# LCR_0.net
KiCad netlist of a schematic drawn in Altium Designer
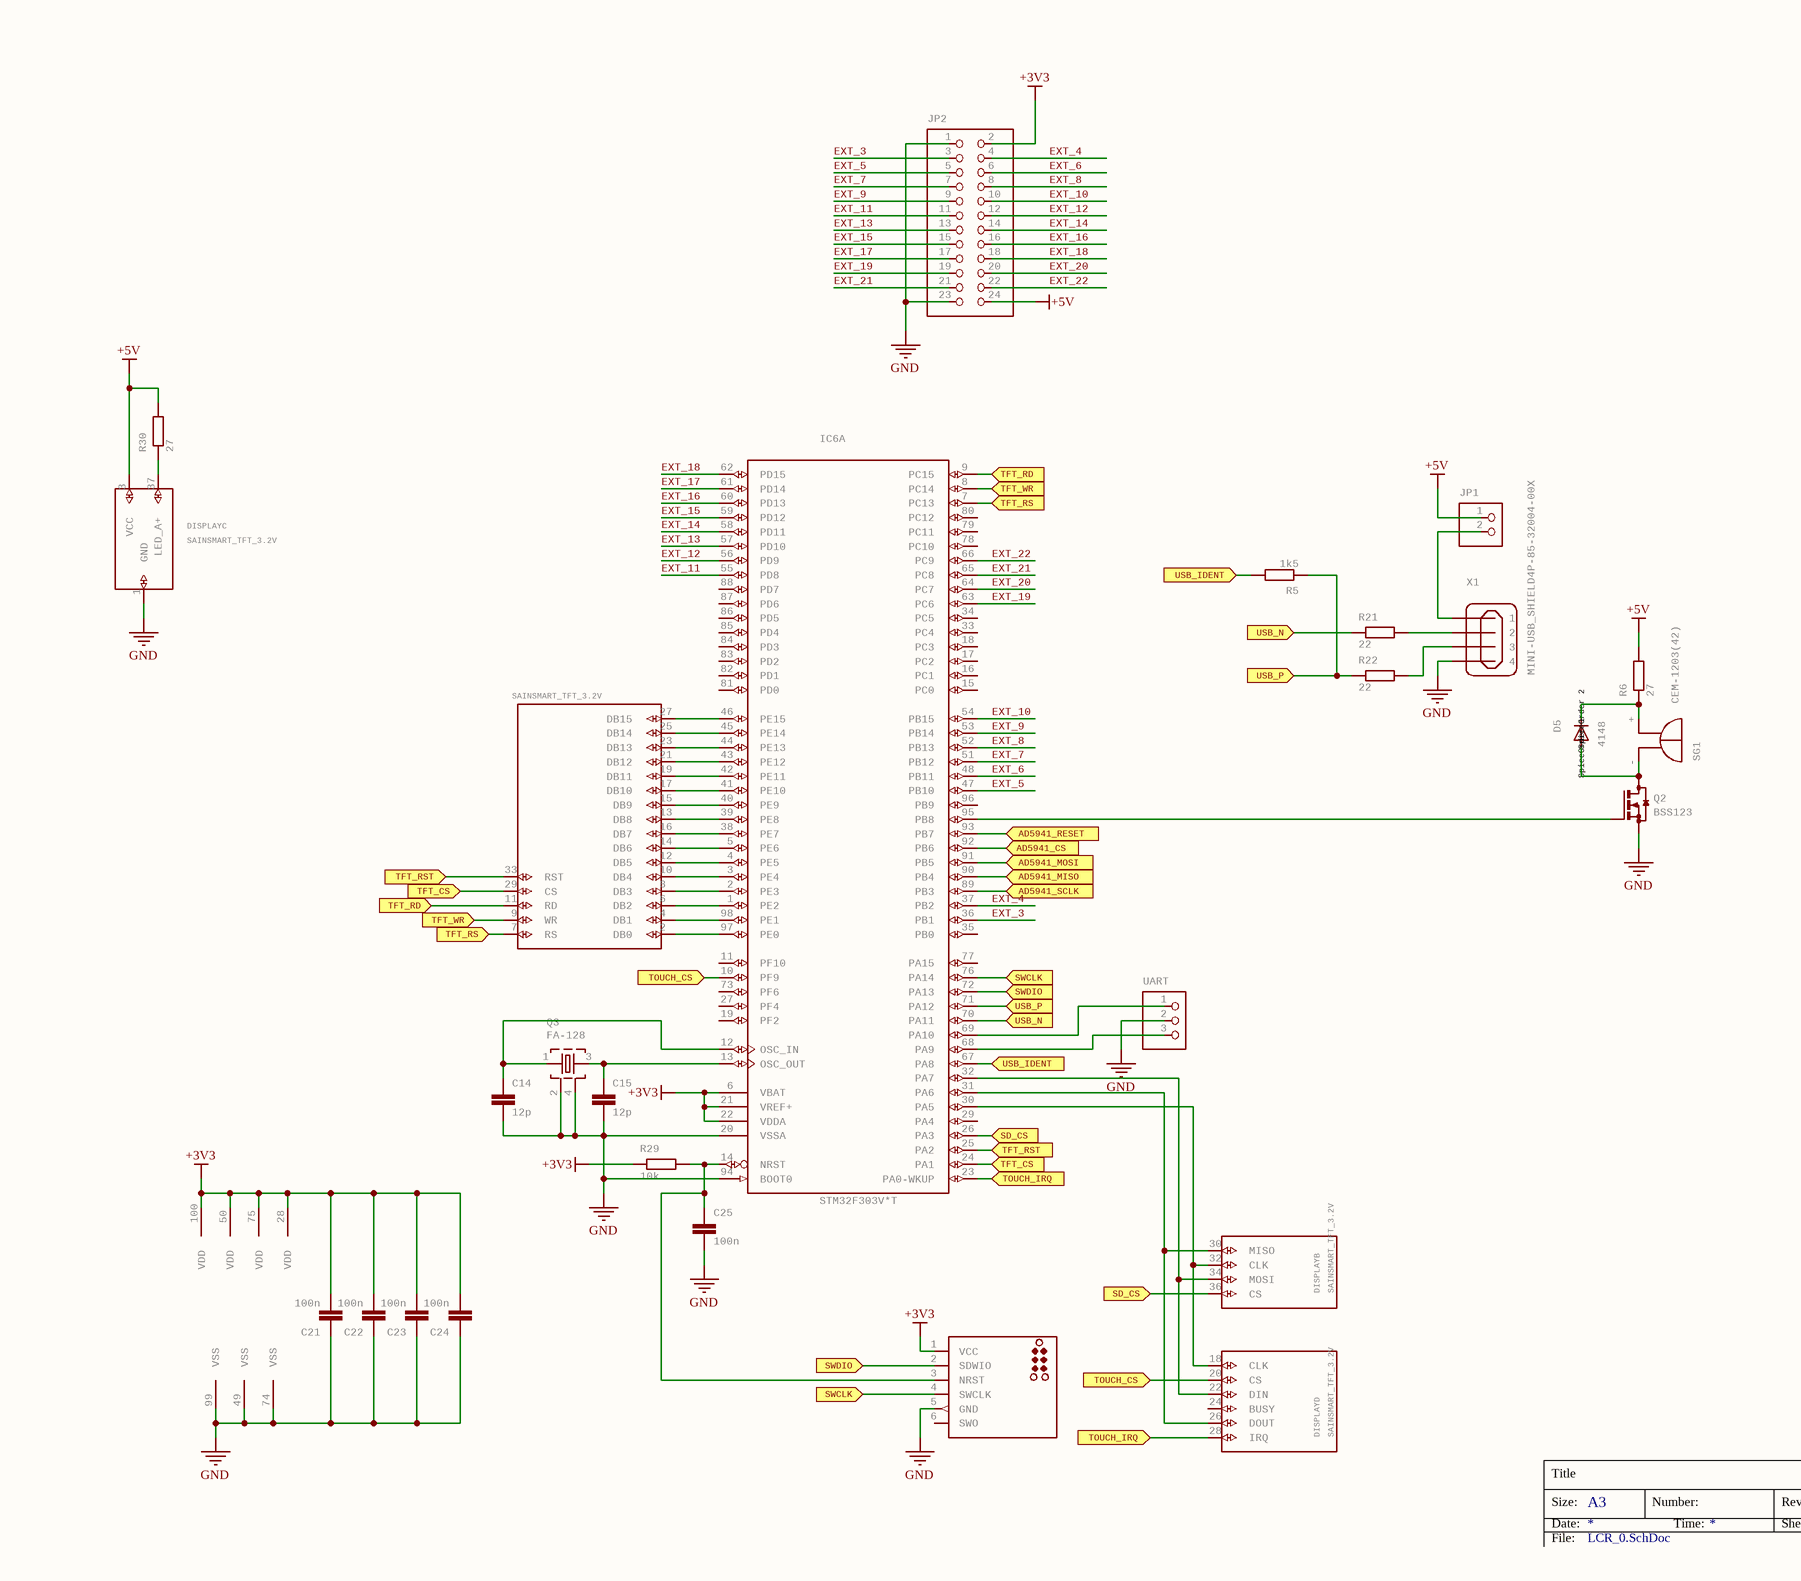
[diagram p0: LCR_0.SchDoc]

(export (version "E")
  (design (tool "Eeschema 10.0.6"))
  (components
    (comp (ref "C14")
      (value "12p")
      (footprint "C0603K")
      (description "CAPACITOR, European symbol")
      (libsource (lib "") (part "C-EUC0603K_1"))
    )
    (comp (ref "C15")
      (value "12p")
      (footprint "C0603K")
      (description "CAPACITOR, European symbol")
      (libsource (lib "") (part "C-EUC0603K_1"))
    )
    (comp (ref "C21")
      (value "100n")
      (footprint "C0603K")
      (description "CAPACITOR, European symbol")
      (libsource (lib "rcl") (part "C-EUC0603K"))
    )
    (comp (ref "C22")
      (value "100n")
      (footprint "C0603K")
      (description "CAPACITOR, European symbol")
      (libsource (lib "rcl") (part "C-EUC0603K"))
    )
    (comp (ref "C23")
      (value "100n")
      (footprint "C0603K")
      (description "CAPACITOR, European symbol")
      (libsource (lib "rcl") (part "C-EUC0603K"))
    )
    (comp (ref "C24")
      (value "100n")
      (footprint "C0603K")
      (description "CAPACITOR, European symbol")
      (libsource (lib "rcl") (part "C-EUC0603K"))
    )
    (comp (ref "C25")
      (value "100n")
      (footprint "C0603K")
      (description "CAPACITOR, European symbol")
      (libsource (lib "") (part "C-EUC0603K_1"))
    )
    (comp (ref "D5")
      (value "4148")
      (footprint "SOD123")
      (description "DIODE")
      (fields (field (name "SPICEORDER1") "SpiceOrder 1") (field (name "SPICEORDER2") "SpiceOrder 2"))
      (libsource (lib "diode") (part "DIODE-SOD123"))
    )
    (comp (ref "DISPLAY")
      (value "SAINSMART_TFT_3.2V")
      (footprint "SAINSMART_ANGLED")
      (libsource (lib "sainsmart") (part "SAINSMART_TFT_3.2V"))
    )
    (comp (ref "IC6")
      (value "STM32F303V*T")
      (footprint "LQFP100")
      (libsource (lib "micro-stm_v3") (part "STM32F303V*T"))
    )
    (comp (ref "J1")
      (value "TC2030-MCP")
      (footprint "TC2030-MCP")
      (libsource (lib "tag-connect") (part "TC2030-MCP"))
    )
    (comp (ref "JP1")
      (value "~")
      (footprint "1X02")
      (description "PIN HEADER")
      (fields (field (name "LIBRARYNAME") "pinhead"))
      (libsource (lib "pinhead") (part "PINHD-1X2"))
    )
    (comp (ref "JP2")
      (value "~")
      (footprint "2X12")
      (description "PIN HEADER")
      (fields (field (name "LIBRARYNAME") "pinhead"))
      (libsource (lib "pinhead") (part "PINHD-2X12"))
    )
    (comp (ref "Q2")
      (value "BSS123")
      (footprint "SOT23")
      (description "N-CHANNEL MOS FET")
      (libsource (lib "transistor-small-signal") (part "BSS123"))
    )
    (comp (ref "Q3")
      (value "FA-128")
      (footprint "FA-128")
      (description "MHz RANGE CRYSTAL UNIT    Source: Epson Toyocom")
      (libsource (lib "crystal") (part "FA-128"))
    )
    (comp (ref "R5")
      (value "1k5")
      (footprint "R0603")
      (description "RESISTOR, European symbol")
      (libsource (lib "resistor") (part "R-EU_R0603"))
    )
    (comp (ref "R6")
      (value "27")
      (footprint "R1206")
      (description "RESISTOR, European symbol")
      (libsource (lib "resistor") (part "R-EU_R1206"))
    )
    (comp (ref "R21")
      (value "22")
      (footprint "R0603")
      (description "RESISTOR, European symbol")
      (libsource (lib "resistor") (part "R-EU_R0603"))
    )
    (comp (ref "R22")
      (value "22")
      (footprint "R0603")
      (description "RESISTOR, European symbol")
      (libsource (lib "resistor") (part "R-EU_R0603"))
    )
    (comp (ref "R29")
      (value "10k")
      (footprint "R0603")
      (description "RESISTOR, European symbol")
      (libsource (lib "resistor") (part "R-EU_R0603"))
    )
    (comp (ref "R30")
      (value "27")
      (footprint "R1206")
      (description "RESISTOR, European symbol")
      (libsource (lib "resistor") (part "R-EU_R1206"))
    )
    (comp (ref "SG1")
      (value "CEM-1203(42)")
      (footprint "F/QMBIII")
      (description "BUZZER    Source: Buerklin")
      (fields (field (name "MF") "MF") (field (name "MPN") "MPN"))
      (libsource (lib "buzzer") (part "F/QMBIII"))
    )
    (comp (ref "UART")
      (value "~")
      (footprint "1X03")
      (description "PIN HEADER")
      (fields (field (name "LIBRARYNAME") "pinhead"))
      (libsource (lib "pinhead") (part "PINHD-1X3"))
    )
    (comp (ref "X1")
      (value "MINI-USB_SHIELD4P-85-32004-00X")
      (footprint "85-32004-00X")
      (description "MINI USB 4 Pol.   Source: www.cypressindustries.com")
      (fields (field (name "MF") "MF") (field (name "MPN") "MPN"))
      (libsource (lib "con-cypressindustries") (part "MINI-USB_SHIELD4P-85-32004-00X"))
    )
  )
  (nets
    (net (code "1") (name "+3V3") (class "Default")
      (node (ref "C21") (pin "2") (pinfunction "2_2") (pintype "passive"))
      (node (ref "C22") (pin "2") (pinfunction "2_2") (pintype "passive"))
      (node (ref "C23") (pin "2") (pinfunction "2_2") (pintype "passive"))
      (node (ref "C24") (pin "2") (pinfunction "2_2") (pintype "passive"))
      (node (ref "IC6") (pin "100") (pinfunction "VDD_100") (pintype "power_in"))
      (node (ref "IC6") (pin "21") (pinfunction "VREF+_21") (pintype "power_in"))
      (node (ref "IC6") (pin "22") (pinfunction "VDDA_22") (pintype "power_in"))
      (node (ref "IC6") (pin "28") (pinfunction "VDD_28") (pintype "power_in"))
      (node (ref "IC6") (pin "50") (pinfunction "VDD_50") (pintype "power_in"))
      (node (ref "IC6") (pin "6") (pinfunction "VBAT_6") (pintype "power_in"))
      (node (ref "IC6") (pin "75") (pinfunction "VDD_75") (pintype "power_in"))
      (node (ref "J1") (pin "1") (pinfunction "VCC_1") (pintype "passive"))
      (node (ref "JP2") (pin "2") (pinfunction "2_2") (pintype "passive"))
      (node (ref "R29") (pin "1") (pinfunction "1_1") (pintype "passive"))
    )
    (net (code "2") (name "+5V") (class "Default")
      (node (ref "DISPLAY") (pin "3") (pinfunction "VCC_3") (pintype "bidirectional"))
      (node (ref "JP1") (pin "1") (pinfunction "1_1") (pintype "passive"))
      (node (ref "JP2") (pin "24") (pinfunction "24_24") (pintype "passive"))
      (node (ref "R30") (pin "2") (pinfunction "2_2") (pintype "passive"))
      (node (ref "R6") (pin "2") (pinfunction "2_2") (pintype "passive"))
    )
    (net (code "3") (name "/AD5941_CS") (class "Default")
      (node (ref "IC6") (pin "92") (pinfunction "PB6_92") (pintype "bidirectional"))
    )
    (net (code "4") (name "/AD5941_MISO") (class "Default")
      (node (ref "IC6") (pin "90") (pinfunction "PB4_90") (pintype "bidirectional"))
    )
    (net (code "5") (name "/AD5941_MOSI") (class "Default")
      (node (ref "IC6") (pin "91") (pinfunction "PB5_91") (pintype "bidirectional"))
    )
    (net (code "6") (name "/AD5941_RESET") (class "Default")
      (node (ref "IC6") (pin "93") (pinfunction "PB7_93") (pintype "bidirectional"))
    )
    (net (code "7") (name "/AD5941_SCLK") (class "Default")
      (node (ref "IC6") (pin "89") (pinfunction "PB3_89") (pintype "bidirectional"))
    )
    (net (code "8") (name "/EXT_3") (class "Default")
      (node (ref "IC6") (pin "36") (pinfunction "PB1_36") (pintype "bidirectional"))
      (node (ref "JP2") (pin "3") (pinfunction "3_3") (pintype "passive"))
    )
    (net (code "9") (name "/EXT_4") (class "Default")
      (node (ref "IC6") (pin "37") (pinfunction "PB2_37") (pintype "bidirectional"))
      (node (ref "JP2") (pin "4") (pinfunction "4_4") (pintype "passive"))
    )
    (net (code "10") (name "/EXT_5") (class "Default")
      (node (ref "IC6") (pin "47") (pinfunction "PB10_47") (pintype "bidirectional"))
      (node (ref "JP2") (pin "5") (pinfunction "5_5") (pintype "passive"))
    )
    (net (code "11") (name "/EXT_6") (class "Default")
      (node (ref "IC6") (pin "48") (pinfunction "PB11_48") (pintype "bidirectional"))
      (node (ref "JP2") (pin "6") (pinfunction "6_6") (pintype "passive"))
    )
    (net (code "12") (name "/EXT_7") (class "Default")
      (node (ref "IC6") (pin "51") (pinfunction "PB12_51") (pintype "bidirectional"))
      (node (ref "JP2") (pin "7") (pinfunction "7_7") (pintype "passive"))
    )
    (net (code "13") (name "/EXT_8") (class "Default")
      (node (ref "IC6") (pin "52") (pinfunction "PB13_52") (pintype "bidirectional"))
      (node (ref "JP2") (pin "8") (pinfunction "8_8") (pintype "passive"))
    )
    (net (code "14") (name "/EXT_9") (class "Default")
      (node (ref "IC6") (pin "53") (pinfunction "PB14_53") (pintype "bidirectional"))
      (node (ref "JP2") (pin "9") (pinfunction "9_9") (pintype "passive"))
    )
    (net (code "15") (name "/EXT_10") (class "Default")
      (node (ref "IC6") (pin "54") (pinfunction "PB15_54") (pintype "bidirectional"))
      (node (ref "JP2") (pin "10") (pinfunction "10_10") (pintype "passive"))
    )
    (net (code "16") (name "/EXT_11") (class "Default")
      (node (ref "IC6") (pin "55") (pinfunction "PD8_55") (pintype "bidirectional"))
      (node (ref "JP2") (pin "11") (pinfunction "11_11") (pintype "passive"))
    )
    (net (code "17") (name "/EXT_12") (class "Default")
      (node (ref "IC6") (pin "56") (pinfunction "PD9_56") (pintype "bidirectional"))
      (node (ref "JP2") (pin "12") (pinfunction "12_12") (pintype "passive"))
    )
    (net (code "18") (name "/EXT_13") (class "Default")
      (node (ref "IC6") (pin "57") (pinfunction "PD10_57") (pintype "bidirectional"))
      (node (ref "JP2") (pin "13") (pinfunction "13_13") (pintype "passive"))
    )
    (net (code "19") (name "/EXT_14") (class "Default")
      (node (ref "IC6") (pin "58") (pinfunction "PD11_58") (pintype "bidirectional"))
      (node (ref "JP2") (pin "14") (pinfunction "14_14") (pintype "passive"))
    )
    (net (code "20") (name "/EXT_15") (class "Default")
      (node (ref "IC6") (pin "59") (pinfunction "PD12_59") (pintype "bidirectional"))
      (node (ref "JP2") (pin "15") (pinfunction "15_15") (pintype "passive"))
    )
    (net (code "21") (name "/EXT_16") (class "Default")
      (node (ref "IC6") (pin "60") (pinfunction "PD13_60") (pintype "bidirectional"))
      (node (ref "JP2") (pin "16") (pinfunction "16_16") (pintype "passive"))
    )
    (net (code "22") (name "/EXT_17") (class "Default")
      (node (ref "IC6") (pin "61") (pinfunction "PD14_61") (pintype "bidirectional"))
      (node (ref "JP2") (pin "17") (pinfunction "17_17") (pintype "passive"))
    )
    (net (code "23") (name "/EXT_18") (class "Default")
      (node (ref "IC6") (pin "62") (pinfunction "PD15_62") (pintype "bidirectional"))
      (node (ref "JP2") (pin "18") (pinfunction "18_18") (pintype "passive"))
    )
    (net (code "24") (name "/EXT_19") (class "Default")
      (node (ref "IC6") (pin "63") (pinfunction "PC6_63") (pintype "bidirectional"))
      (node (ref "JP2") (pin "19") (pinfunction "19_19") (pintype "passive"))
    )
    (net (code "25") (name "/EXT_20") (class "Default")
      (node (ref "IC6") (pin "64") (pinfunction "PC7_64") (pintype "bidirectional"))
      (node (ref "JP2") (pin "20") (pinfunction "20_20") (pintype "passive"))
    )
    (net (code "26") (name "/EXT_21") (class "Default")
      (node (ref "IC6") (pin "65") (pinfunction "PC8_65") (pintype "bidirectional"))
      (node (ref "JP2") (pin "21") (pinfunction "21_21") (pintype "passive"))
    )
    (net (code "27") (name "/EXT_22") (class "Default")
      (node (ref "IC6") (pin "66") (pinfunction "PC9_66") (pintype "bidirectional"))
      (node (ref "JP2") (pin "22") (pinfunction "22_22") (pintype "passive"))
    )
    (net (code "28") (name "/SD_CS") (class "Default")
      (node (ref "DISPLAY") (pin "36") (pinfunction "CS_36") (pintype "bidirectional"))
      (node (ref "IC6") (pin "26") (pinfunction "PA3_26") (pintype "bidirectional"))
    )
    (net (code "29") (name "/SWCLK") (class "Default")
      (node (ref "IC6") (pin "76") (pinfunction "PA14_76") (pintype "bidirectional"))
      (node (ref "J1") (pin "4") (pinfunction "SWCLK_4") (pintype "bidirectional"))
    )
    (net (code "30") (name "/SWDIO") (class "Default")
      (node (ref "IC6") (pin "72") (pinfunction "PA13_72") (pintype "bidirectional"))
      (node (ref "J1") (pin "2") (pinfunction "SDWIO_2") (pintype "power_in"))
    )
    (net (code "31") (name "/TFT_CS") (class "Default")
      (node (ref "DISPLAY") (pin "29") (pinfunction "CS_29") (pintype "bidirectional"))
      (node (ref "IC6") (pin "24") (pinfunction "PA1_24") (pintype "bidirectional"))
    )
    (net (code "32") (name "/TFT_RD") (class "Default")
      (node (ref "DISPLAY") (pin "11") (pinfunction "RD_11") (pintype "bidirectional"))
      (node (ref "IC6") (pin "9") (pinfunction "PC15_9") (pintype "bidirectional"))
    )
    (net (code "33") (name "/TFT_RS") (class "Default")
      (node (ref "DISPLAY") (pin "7") (pinfunction "RS_7") (pintype "bidirectional"))
      (node (ref "IC6") (pin "7") (pinfunction "PC13_7") (pintype "bidirectional"))
    )
    (net (code "34") (name "/TFT_RST") (class "Default")
      (node (ref "DISPLAY") (pin "33") (pinfunction "RST_33") (pintype "bidirectional"))
      (node (ref "IC6") (pin "25") (pinfunction "PA2_25") (pintype "bidirectional"))
    )
    (net (code "35") (name "/TFT_WR") (class "Default")
      (node (ref "DISPLAY") (pin "9") (pinfunction "WR_9") (pintype "bidirectional"))
      (node (ref "IC6") (pin "8") (pinfunction "PC14_8") (pintype "bidirectional"))
    )
    (net (code "36") (name "/TOUCH_CS") (class "Default")
      (node (ref "DISPLAY") (pin "20") (pinfunction "CS_20") (pintype "bidirectional"))
      (node (ref "IC6") (pin "10") (pinfunction "PF9_10") (pintype "bidirectional"))
    )
    (net (code "37") (name "/TOUCH_IRQ") (class "Default")
      (node (ref "DISPLAY") (pin "28") (pinfunction "IRQ_28") (pintype "bidirectional"))
      (node (ref "IC6") (pin "23") (pinfunction "PA0-WKUP_23") (pintype "bidirectional"))
    )
    (net (code "38") (name "/USB_IDENT") (class "Default")
      (node (ref "IC6") (pin "67") (pinfunction "PA8_67") (pintype "bidirectional"))
      (node (ref "R5") (pin "2") (pinfunction "2_2") (pintype "passive"))
    )
    (net (code "39") (name "/USB_N") (class "Default")
      (node (ref "IC6") (pin "70") (pinfunction "PA11_70") (pintype "bidirectional"))
      (node (ref "R21") (pin "1") (pinfunction "1_1") (pintype "passive"))
    )
    (net (code "40") (name "/USB_P") (class "Default")
      (node (ref "IC6") (pin "71") (pinfunction "PA12_71") (pintype "bidirectional"))
      (node (ref "R22") (pin "1") (pinfunction "1_1") (pintype "passive"))
      (node (ref "R5") (pin "1") (pinfunction "1_1") (pintype "passive"))
    )
    (net (code "41") (name "GND") (class "Default")
      (node (ref "C14") (pin "2") (pinfunction "2_2") (pintype "passive"))
      (node (ref "C15") (pin "2") (pinfunction "2_2") (pintype "passive"))
      (node (ref "C21") (pin "1") (pinfunction "1_1") (pintype "passive"))
      (node (ref "C22") (pin "1") (pinfunction "1_1") (pintype "passive"))
      (node (ref "C23") (pin "1") (pinfunction "1_1") (pintype "passive"))
      (node (ref "C24") (pin "1") (pinfunction "1_1") (pintype "passive"))
      (node (ref "C25") (pin "2") (pinfunction "2_2") (pintype "passive"))
      (node (ref "DISPLAY") (pin "1") (pinfunction "GND_1") (pintype "bidirectional"))
      (node (ref "IC6") (pin "20") (pinfunction "VSSA_20") (pintype "power_in"))
      (node (ref "IC6") (pin "49") (pinfunction "VSS_49") (pintype "power_in"))
      (node (ref "IC6") (pin "74") (pinfunction "VSS_74") (pintype "power_in"))
      (node (ref "IC6") (pin "94") (pinfunction "BOOT0_94") (pintype "input"))
      (node (ref "IC6") (pin "99") (pinfunction "VSS_99") (pintype "power_in"))
      (node (ref "J1") (pin "5") (pinfunction "GND_5") (pintype "output"))
      (node (ref "JP2") (pin "1") (pinfunction "1_1") (pintype "passive"))
      (node (ref "JP2") (pin "23") (pinfunction "23_23") (pintype "passive"))
      (node (ref "Q2") (pin "2") (pinfunction "S_2") (pintype "passive"))
      (node (ref "Q3") (pin "2") (pinfunction "2_2") (pintype "passive"))
      (node (ref "Q3") (pin "4") (pinfunction "4_4") (pintype "passive"))
      (node (ref "UART") (pin "2") (pinfunction "2_2") (pintype "passive"))
      (node (ref "X1") (pin "4") (pinfunction "4_4") (pintype "passive"))
    )
    (net (code "42") (name "Net-(DISPLAYA-DB0)") (class "Default")
      (node (ref "DISPLAY") (pin "2") (pinfunction "DB0_2") (pintype "bidirectional"))
      (node (ref "IC6") (pin "97") (pinfunction "PE0_97") (pintype "bidirectional"))
    )
    (net (code "43") (name "Net-(DISPLAYA-DB1)") (class "Default")
      (node (ref "DISPLAY") (pin "4") (pinfunction "DB1_4") (pintype "bidirectional"))
      (node (ref "IC6") (pin "98") (pinfunction "PE1_98") (pintype "bidirectional"))
    )
    (net (code "44") (name "Net-(DISPLAYA-DB2)") (class "Default")
      (node (ref "DISPLAY") (pin "6") (pinfunction "DB2_6") (pintype "bidirectional"))
      (node (ref "IC6") (pin "1") (pinfunction "PE2_1") (pintype "bidirectional"))
    )
    (net (code "45") (name "Net-(DISPLAYA-DB3)") (class "Default")
      (node (ref "DISPLAY") (pin "8") (pinfunction "DB3_8") (pintype "bidirectional"))
      (node (ref "IC6") (pin "2") (pinfunction "PE3_2") (pintype "bidirectional"))
    )
    (net (code "46") (name "Net-(DISPLAYA-DB4)") (class "Default")
      (node (ref "DISPLAY") (pin "10") (pinfunction "DB4_10") (pintype "bidirectional"))
      (node (ref "IC6") (pin "3") (pinfunction "PE4_3") (pintype "bidirectional"))
    )
    (net (code "47") (name "Net-(DISPLAYA-DB5)") (class "Default")
      (node (ref "DISPLAY") (pin "12") (pinfunction "DB5_12") (pintype "bidirectional"))
      (node (ref "IC6") (pin "4") (pinfunction "PE5_4") (pintype "bidirectional"))
    )
    (net (code "48") (name "Net-(DISPLAYA-DB6)") (class "Default")
      (node (ref "DISPLAY") (pin "14") (pinfunction "DB6_14") (pintype "bidirectional"))
      (node (ref "IC6") (pin "5") (pinfunction "PE6_5") (pintype "bidirectional"))
    )
    (net (code "49") (name "Net-(DISPLAYA-DB7)") (class "Default")
      (node (ref "DISPLAY") (pin "16") (pinfunction "DB7_16") (pintype "bidirectional"))
      (node (ref "IC6") (pin "38") (pinfunction "PE7_38") (pintype "bidirectional"))
    )
    (net (code "50") (name "Net-(DISPLAYA-DB8)") (class "Default")
      (node (ref "DISPLAY") (pin "13") (pinfunction "DB8_13") (pintype "bidirectional"))
      (node (ref "IC6") (pin "39") (pinfunction "PE8_39") (pintype "bidirectional"))
    )
    (net (code "51") (name "Net-(DISPLAYA-DB9)") (class "Default")
      (node (ref "DISPLAY") (pin "15") (pinfunction "DB9_15") (pintype "bidirectional"))
      (node (ref "IC6") (pin "40") (pinfunction "PE9_40") (pintype "bidirectional"))
    )
    (net (code "52") (name "Net-(DISPLAYA-DB10)") (class "Default")
      (node (ref "DISPLAY") (pin "17") (pinfunction "DB10_17") (pintype "bidirectional"))
      (node (ref "IC6") (pin "41") (pinfunction "PE10_41") (pintype "bidirectional"))
    )
    (net (code "53") (name "Net-(DISPLAYA-DB11)") (class "Default")
      (node (ref "DISPLAY") (pin "19") (pinfunction "DB11_19") (pintype "bidirectional"))
      (node (ref "IC6") (pin "42") (pinfunction "PE11_42") (pintype "bidirectional"))
    )
    (net (code "54") (name "Net-(DISPLAYA-DB12)") (class "Default")
      (node (ref "DISPLAY") (pin "21") (pinfunction "DB12_21") (pintype "bidirectional"))
      (node (ref "IC6") (pin "43") (pinfunction "PE12_43") (pintype "bidirectional"))
    )
    (net (code "55") (name "Net-(DISPLAYA-DB13)") (class "Default")
      (node (ref "DISPLAY") (pin "23") (pinfunction "DB13_23") (pintype "bidirectional"))
      (node (ref "IC6") (pin "44") (pinfunction "PE13_44") (pintype "bidirectional"))
    )
    (net (code "56") (name "Net-(DISPLAYA-DB14)") (class "Default")
      (node (ref "DISPLAY") (pin "25") (pinfunction "DB14_25") (pintype "bidirectional"))
      (node (ref "IC6") (pin "45") (pinfunction "PE14_45") (pintype "bidirectional"))
    )
    (net (code "57") (name "Net-(DISPLAYA-DB15)") (class "Default")
      (node (ref "DISPLAY") (pin "27") (pinfunction "DB15_27") (pintype "bidirectional"))
      (node (ref "IC6") (pin "46") (pinfunction "PE15_46") (pintype "bidirectional"))
    )
    (net (code "58") (name "Net-(DISPLAYB-CLK)") (class "Default")
      (node (ref "DISPLAY") (pin "18") (pinfunction "CLK_18") (pintype "bidirectional"))
      (node (ref "DISPLAY") (pin "32") (pinfunction "CLK_32") (pintype "bidirectional"))
      (node (ref "IC6") (pin "30") (pinfunction "PA5_30") (pintype "bidirectional"))
    )
    (net (code "59") (name "Net-(DISPLAYB-MISO)") (class "Default")
      (node (ref "DISPLAY") (pin "26") (pinfunction "DOUT_26") (pintype "bidirectional"))
      (node (ref "DISPLAY") (pin "30") (pinfunction "MISO_30") (pintype "bidirectional"))
      (node (ref "IC6") (pin "31") (pinfunction "PA6_31") (pintype "bidirectional"))
    )
    (net (code "60") (name "Net-(DISPLAYB-MOSI)") (class "Default")
      (node (ref "DISPLAY") (pin "22") (pinfunction "DIN_22") (pintype "bidirectional"))
      (node (ref "DISPLAY") (pin "34") (pinfunction "MOSI_34") (pintype "bidirectional"))
      (node (ref "IC6") (pin "32") (pinfunction "PA7_32") (pintype "bidirectional"))
    )
    (net (code "61") (name "Net-(DISPLAYC-LED_A+)") (class "Default")
      (node (ref "DISPLAY") (pin "37") (pinfunction "LED_A+_37") (pintype "bidirectional"))
      (node (ref "R30") (pin "1") (pinfunction "1_1") (pintype "passive"))
    )
    (net (code "62") (name "Net-(IC6A-NRST)") (class "Default")
      (node (ref "C25") (pin "1") (pinfunction "1_1") (pintype "passive"))
      (node (ref "IC6") (pin "14") (pinfunction "NRST_14") (pintype "bidirectional"))
      (node (ref "J1") (pin "3") (pinfunction "NRST_3") (pintype "power_in"))
      (node (ref "R29") (pin "2") (pinfunction "2_2") (pintype "passive"))
    )
    (net (code "63") (name "Net-(IC6A-OSC_IN)") (class "Default")
      (node (ref "C14") (pin "1") (pinfunction "1_1") (pintype "passive"))
      (node (ref "IC6") (pin "12") (pinfunction "OSC_IN_12") (pintype "bidirectional"))
      (node (ref "Q3") (pin "1") (pinfunction "1_1") (pintype "passive"))
    )
    (net (code "64") (name "Net-(IC6A-OSC_OUT)") (class "Default")
      (node (ref "C15") (pin "1") (pinfunction "1_1") (pintype "passive"))
      (node (ref "IC6") (pin "13") (pinfunction "OSC_OUT_13") (pintype "bidirectional"))
      (node (ref "Q3") (pin "3") (pinfunction "3_3") (pintype "passive"))
    )
    (net (code "65") (name "Net-(IC6A-PA9)") (class "Default")
      (node (ref "IC6") (pin "68") (pinfunction "PA9_68") (pintype "bidirectional"))
      (node (ref "UART") (pin "3") (pinfunction "3_3") (pintype "passive"))
    )
    (net (code "66") (name "Net-(IC6A-PA10)") (class "Default")
      (node (ref "IC6") (pin "69") (pinfunction "PA10_69") (pintype "bidirectional"))
      (node (ref "UART") (pin "1") (pinfunction "1_1") (pintype "passive"))
    )
    (net (code "67") (name "Net-(IC6A-PB8)") (class "Default")
      (node (ref "IC6") (pin "95") (pinfunction "PB8_95") (pintype "bidirectional"))
      (node (ref "Q2") (pin "1") (pinfunction "G_1") (pintype "passive"))
    )
    (net (code "68") (name "Net-(JP1-Pad2)") (class "Default")
      (node (ref "JP1") (pin "2") (pinfunction "2_2") (pintype "passive"))
      (node (ref "X1") (pin "1") (pinfunction "1_1") (pintype "passive"))
    )
    (net (code "69") (name "Net-(Q2-D)") (class "Default")
      (node (ref "D5") (pin "A") (pinfunction "A_A") (pintype "passive"))
      (node (ref "Q2") (pin "3") (pinfunction "D_3") (pintype "passive"))
      (node (ref "SG1") (pin "-") (pinfunction "+_-") (pintype "passive"))
    )
    (net (code "70") (name "Net-(R21-Pad2)") (class "Default")
      (node (ref "R21") (pin "2") (pinfunction "2_2") (pintype "passive"))
      (node (ref "X1") (pin "2") (pinfunction "2_2") (pintype "passive"))
    )
    (net (code "71") (name "Net-(R22-Pad2)") (class "Default")
      (node (ref "R22") (pin "2") (pinfunction "2_2") (pintype "passive"))
      (node (ref "X1") (pin "3") (pinfunction "3_3") (pintype "passive"))
    )
    (net (code "72") (name "Net-(SG1--)") (class "Default")
      (node (ref "D5") (pin "C") (pinfunction "C_C") (pintype "passive"))
      (node (ref "R6") (pin "1") (pinfunction "1_1") (pintype "passive"))
      (node (ref "SG1") (pin "+") (pinfunction "-_+") (pintype "passive"))
    )
    (net (code "73") (name "unconnected-(DISPLAYD-BUSY-Pad24)") (class "Default")
      (node (ref "DISPLAY") (pin "24") (pinfunction "BUSY_24") (pintype "bidirectional"))
    )
    (net (code "74") (name "unconnected-(IC6A-PA4-Pad29)") (class "Default")
      (node (ref "IC6") (pin "29") (pinfunction "PA4_29") (pintype "bidirectional"))
    )
    (net (code "75") (name "unconnected-(IC6A-PA15-Pad77)") (class "Default")
      (node (ref "IC6") (pin "77") (pinfunction "PA15_77") (pintype "bidirectional"))
    )
    (net (code "76") (name "unconnected-(IC6A-PB0-Pad35)") (class "Default")
      (node (ref "IC6") (pin "35") (pinfunction "PB0_35") (pintype "bidirectional"))
    )
    (net (code "77") (name "unconnected-(IC6A-PB9-Pad96)") (class "Default")
      (node (ref "IC6") (pin "96") (pinfunction "PB9_96") (pintype "bidirectional"))
    )
    (net (code "78") (name "unconnected-(IC6A-PC0-Pad15)") (class "Default")
      (node (ref "IC6") (pin "15") (pinfunction "PC0_15") (pintype "bidirectional"))
    )
    (net (code "79") (name "unconnected-(IC6A-PC1-Pad16)") (class "Default")
      (node (ref "IC6") (pin "16") (pinfunction "PC1_16") (pintype "bidirectional"))
    )
    (net (code "80") (name "unconnected-(IC6A-PC2-Pad17)") (class "Default")
      (node (ref "IC6") (pin "17") (pinfunction "PC2_17") (pintype "bidirectional"))
    )
    (net (code "81") (name "unconnected-(IC6A-PC3-Pad18)") (class "Default")
      (node (ref "IC6") (pin "18") (pinfunction "PC3_18") (pintype "bidirectional"))
    )
    (net (code "82") (name "unconnected-(IC6A-PC4-Pad33)") (class "Default")
      (node (ref "IC6") (pin "33") (pinfunction "PC4_33") (pintype "bidirectional"))
    )
    (net (code "83") (name "unconnected-(IC6A-PC5-Pad34)") (class "Default")
      (node (ref "IC6") (pin "34") (pinfunction "PC5_34") (pintype "bidirectional"))
    )
    (net (code "84") (name "unconnected-(IC6A-PC10-Pad78)") (class "Default")
      (node (ref "IC6") (pin "78") (pinfunction "PC10_78") (pintype "bidirectional"))
    )
    (net (code "85") (name "unconnected-(IC6A-PC11-Pad79)") (class "Default")
      (node (ref "IC6") (pin "79") (pinfunction "PC11_79") (pintype "bidirectional"))
    )
    (net (code "86") (name "unconnected-(IC6A-PC12-Pad80)") (class "Default")
      (node (ref "IC6") (pin "80") (pinfunction "PC12_80") (pintype "bidirectional"))
    )
    (net (code "87") (name "unconnected-(IC6A-PD0-Pad81)") (class "Default")
      (node (ref "IC6") (pin "81") (pinfunction "PD0_81") (pintype "bidirectional"))
    )
    (net (code "88") (name "unconnected-(IC6A-PD1-Pad82)") (class "Default")
      (node (ref "IC6") (pin "82") (pinfunction "PD1_82") (pintype "bidirectional"))
    )
    (net (code "89") (name "unconnected-(IC6A-PD2-Pad83)") (class "Default")
      (node (ref "IC6") (pin "83") (pinfunction "PD2_83") (pintype "bidirectional"))
    )
    (net (code "90") (name "unconnected-(IC6A-PD3-Pad84)") (class "Default")
      (node (ref "IC6") (pin "84") (pinfunction "PD3_84") (pintype "bidirectional"))
    )
    (net (code "91") (name "unconnected-(IC6A-PD4-Pad85)") (class "Default")
      (node (ref "IC6") (pin "85") (pinfunction "PD4_85") (pintype "bidirectional"))
    )
    (net (code "92") (name "unconnected-(IC6A-PD5-Pad86)") (class "Default")
      (node (ref "IC6") (pin "86") (pinfunction "PD5_86") (pintype "bidirectional"))
    )
    (net (code "93") (name "unconnected-(IC6A-PD6-Pad87)") (class "Default")
      (node (ref "IC6") (pin "87") (pinfunction "PD6_87") (pintype "bidirectional"))
    )
    (net (code "94") (name "unconnected-(IC6A-PD7-Pad88)") (class "Default")
      (node (ref "IC6") (pin "88") (pinfunction "PD7_88") (pintype "bidirectional"))
    )
    (net (code "95") (name "unconnected-(IC6A-PF2-Pad19)") (class "Default")
      (node (ref "IC6") (pin "19") (pinfunction "PF2_19") (pintype "bidirectional"))
    )
    (net (code "96") (name "unconnected-(IC6A-PF4-Pad27)") (class "Default")
      (node (ref "IC6") (pin "27") (pinfunction "PF4_27") (pintype "bidirectional"))
    )
    (net (code "97") (name "unconnected-(IC6A-PF6-Pad73)") (class "Default")
      (node (ref "IC6") (pin "73") (pinfunction "PF6_73") (pintype "bidirectional"))
    )
    (net (code "98") (name "unconnected-(IC6A-PF10-Pad11)") (class "Default")
      (node (ref "IC6") (pin "11") (pinfunction "PF10_11") (pintype "bidirectional"))
    )
    (net (code "99") (name "unconnected-(J1-SWO-Pad6)") (class "Default")
      (node (ref "J1") (pin "6") (pinfunction "SWO_6") (pintype "bidirectional"))
    )
  )
)
